# Front_Roof_Enclosure.net
KiCad netlist of a schematic drawn in Altium Designer
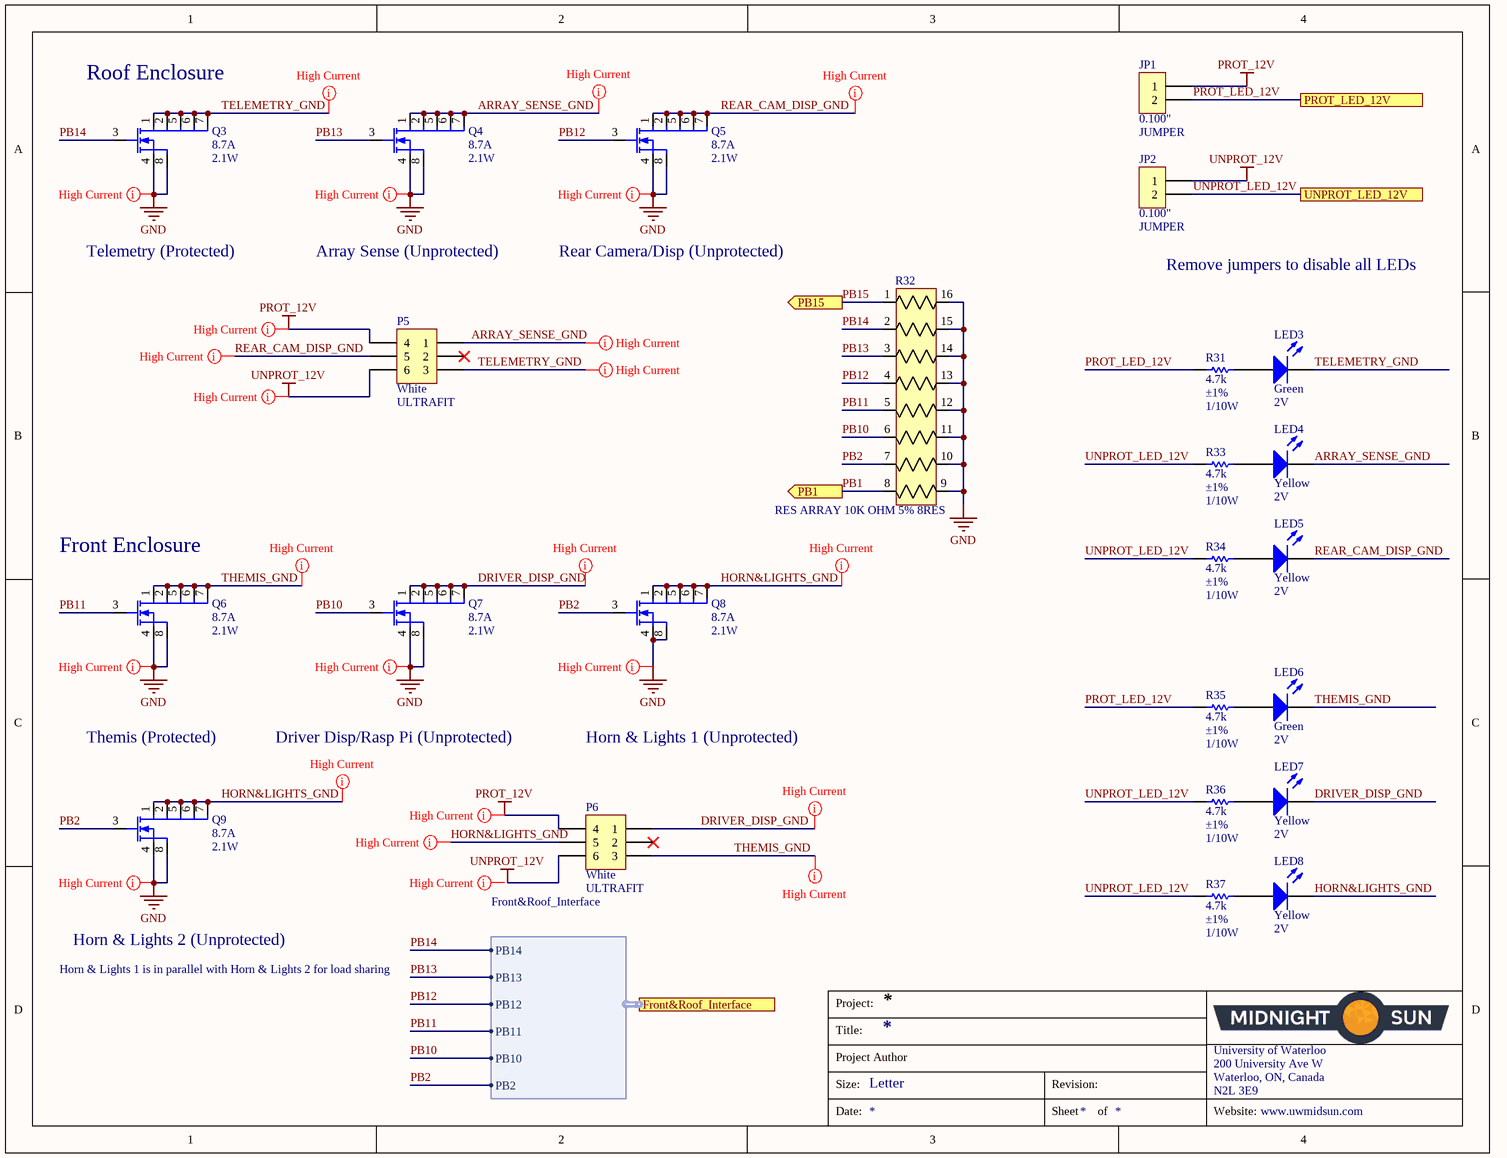
[diagram p0: Front&Roof_Enclosure.SchDoc]

(export (version "E")
  (design (tool "Eeschema 10.0.6"))
  (components
    (comp (ref "JP1")
      (value "JUMPER")
      (footprint "CONN 2POS JUMPER 0.1\"")
      (description "2 Positions Header Connector Through Hole Gold")
      (fields
        (field (name "MANUFACTURER") "Omron Electronics Inc-EMC Div")
        (field (name "MANUFACTURER PART NUMBER") "XG8T-0231")
        (field (name "ROW SPACING - MATING") "0.100\"")
        (field (name "TYPE") "JUMPER")
      )
      (libsource (lib "Schematic Diagrams") (part "CONN 2POS JUMPER 0.1{dblquote}"))
    )
    (comp (ref "JP2")
      (value "JUMPER")
      (footprint "CONN 2POS JUMPER 0.1\"")
      (description "2 Positions Header Connector Through Hole Gold")
      (fields
        (field (name "MANUFACTURER") "Omron Electronics Inc-EMC Div")
        (field (name "MANUFACTURER PART NUMBER") "XG8T-0231")
        (field (name "ROW SPACING - MATING") "0.100\"")
        (field (name "TYPE") "JUMPER")
      )
      (libsource (lib "Schematic Diagrams") (part "CONN 2POS JUMPER 0.1{dblquote}"))
    )
    (comp (ref "LED3")
      (value "LED GREEN CLEAR 2V 0603")
      (footprint "LED_0603")
      (description "Green 572nm LED Indication - Discrete 2V 0603 (1608 Metric)")
      (fields
        (field (name "COLOR") "Green")
        (field (name "VOLTAGE - FORWARD (VF) (TYP)") "2V")
        (field (name "MANUFACTURER") "Wurth Electronics Inc.")
        (field (name "MANUFACTURER PART NUMBER") "150060VS75000")
      )
      (libsource (lib "Schematic Diagrams") (part "LED GREEN CLEAR 2V 0603"))
    )
    (comp (ref "LED4")
      (value "LED YELLOW CLEAR 2.1V 0603")
      (footprint "LED_0603")
      (description "Yellow 590nm LED Indication - Discrete 2V 0603 (1608 Metric)")
      (fields
        (field (name "VOLTAGE - FORWARD (VF) (TYP)") "2V")
        (field (name "MANUFACTURER") "Wurth Electronics Inc.")
        (field (name "MANUFACTURER PART NUMBER") "150060YS75000")
      )
      (libsource (lib "Schematic Diagrams") (part "LED YELLOW CLEAR 2.1V 0603"))
    )
    (comp (ref "LED5")
      (value "LED YELLOW CLEAR 2.1V 0603")
      (footprint "LED_0603")
      (description "Yellow 590nm LED Indication - Discrete 2V 0603 (1608 Metric)")
      (fields
        (field (name "VOLTAGE - FORWARD (VF) (TYP)") "2V")
        (field (name "MANUFACTURER") "Wurth Electronics Inc.")
        (field (name "MANUFACTURER PART NUMBER") "150060YS75000")
      )
      (libsource (lib "Schematic Diagrams") (part "LED YELLOW CLEAR 2.1V 0603"))
    )
    (comp (ref "LED6")
      (value "LED GREEN CLEAR 2V 0603")
      (footprint "LED_0603")
      (description "Green 572nm LED Indication - Discrete 2V 0603 (1608 Metric)")
      (fields
        (field (name "COLOR") "Green")
        (field (name "VOLTAGE - FORWARD (VF) (TYP)") "2V")
        (field (name "MANUFACTURER") "Wurth Electronics Inc.")
        (field (name "MANUFACTURER PART NUMBER") "150060VS75000")
      )
      (libsource (lib "Schematic Diagrams") (part "LED GREEN CLEAR 2V 0603"))
    )
    (comp (ref "LED7")
      (value "LED YELLOW CLEAR 2.1V 0603")
      (footprint "LED_0603")
      (description "Yellow 590nm LED Indication - Discrete 2V 0603 (1608 Metric)")
      (fields
        (field (name "VOLTAGE - FORWARD (VF) (TYP)") "2V")
        (field (name "MANUFACTURER") "Wurth Electronics Inc.")
        (field (name "MANUFACTURER PART NUMBER") "150060YS75000")
      )
      (libsource (lib "Schematic Diagrams") (part "LED YELLOW CLEAR 2.1V 0603"))
    )
    (comp (ref "LED8")
      (value "LED YELLOW CLEAR 2.1V 0603")
      (footprint "LED_0603")
      (description "Yellow 590nm LED Indication - Discrete 2V 0603 (1608 Metric)")
      (fields
        (field (name "VOLTAGE - FORWARD (VF) (TYP)") "2V")
        (field (name "MANUFACTURER") "Wurth Electronics Inc.")
        (field (name "MANUFACTURER PART NUMBER") "150060YS75000")
      )
      (libsource (lib "Schematic Diagrams") (part "LED YELLOW CLEAR 2.1V 0603"))
    )
    (comp (ref "P5")
      (value "CONN 6POS ULTRA-FIT NATURAL COLOR 0.138\"")
      (footprint "CONN, 6POS ULTRA-FIT - NATURAL COLOR")
      (description "6 Positions Header Connector 0.138\" (3.50mm) Through Hole Tin")
      (fields (field (name "INSULATION COLOR") "White") (field (name "SERIES") "ULTRAFIT"))
      (libsource (lib "Schematic Diagrams") (part "CONN 6POS ULTRA-FIT NATURAL COLOR 0.138{dblquote}"))
    )
    (comp (ref "P6")
      (value "CONN 6POS ULTRA-FIT NATURAL COLOR 0.138\"")
      (footprint "CONN, 6POS ULTRA-FIT - NATURAL COLOR")
      (description "6 Positions Header Connector 0.138\" (3.50mm) Through Hole Tin")
      (fields (field (name "INSULATION COLOR") "White") (field (name "SERIES") "ULTRAFIT"))
      (libsource (lib "Schematic Diagrams") (part "CONN 6POS ULTRA-FIT NATURAL COLOR 0.138{dblquote}"))
    )
    (comp (ref "Q3")
      (value "MOSFET N-CH 30V 8.7A 2.1W 6-PQFN (2x2)")
      (footprint "MOSFET N-CH 30V 12A 2mmx2mm PQFN")
      (fields
        (field (name "CURRENT - CONTINUOUS DRAIN (ID) @ 25°C") "8.7A")
        (field (name "POWER DISSIPATION (MAX)") "2.1W")
      )
      (libsource (lib "Schematic Diagrams") (part "MOSFET N-CH 30V 8.7A 2.1W 6-PQFN (2x2)"))
    )
    (comp (ref "Q4")
      (value "MOSFET N-CH 30V 8.7A 2.1W 6-PQFN (2x2)")
      (footprint "MOSFET N-CH 30V 12A 2mmx2mm PQFN")
      (fields
        (field (name "CURRENT - CONTINUOUS DRAIN (ID) @ 25°C") "8.7A")
        (field (name "POWER DISSIPATION (MAX)") "2.1W")
      )
      (libsource (lib "Schematic Diagrams") (part "MOSFET N-CH 30V 8.7A 2.1W 6-PQFN (2x2)"))
    )
    (comp (ref "Q5")
      (value "MOSFET N-CH 30V 8.7A 2.1W 6-PQFN (2x2)")
      (footprint "MOSFET N-CH 30V 12A 2mmx2mm PQFN")
      (fields
        (field (name "CURRENT - CONTINUOUS DRAIN (ID) @ 25°C") "8.7A")
        (field (name "POWER DISSIPATION (MAX)") "2.1W")
      )
      (libsource (lib "Schematic Diagrams") (part "MOSFET N-CH 30V 8.7A 2.1W 6-PQFN (2x2)"))
    )
    (comp (ref "Q6")
      (value "MOSFET N-CH 30V 8.7A 2.1W 6-PQFN (2x2)")
      (footprint "MOSFET N-CH 30V 12A 2mmx2mm PQFN")
      (fields
        (field (name "CURRENT - CONTINUOUS DRAIN (ID) @ 25°C") "8.7A")
        (field (name "POWER DISSIPATION (MAX)") "2.1W")
      )
      (libsource (lib "Schematic Diagrams") (part "MOSFET N-CH 30V 8.7A 2.1W 6-PQFN (2x2)"))
    )
    (comp (ref "Q7")
      (value "MOSFET N-CH 30V 8.7A 2.1W 6-PQFN (2x2)")
      (footprint "MOSFET N-CH 30V 12A 2mmx2mm PQFN")
      (fields
        (field (name "CURRENT - CONTINUOUS DRAIN (ID) @ 25°C") "8.7A")
        (field (name "POWER DISSIPATION (MAX)") "2.1W")
      )
      (libsource (lib "Schematic Diagrams") (part "MOSFET N-CH 30V 8.7A 2.1W 6-PQFN (2x2)"))
    )
    (comp (ref "Q8")
      (value "MOSFET N-CH 30V 8.7A 2.1W 6-PQFN (2x2)")
      (footprint "MOSFET N-CH 30V 12A 2mmx2mm PQFN")
      (fields
        (field (name "CURRENT - CONTINUOUS DRAIN (ID) @ 25°C") "8.7A")
        (field (name "POWER DISSIPATION (MAX)") "2.1W")
      )
      (libsource (lib "Schematic Diagrams") (part "MOSFET N-CH 30V 8.7A 2.1W 6-PQFN (2x2)"))
    )
    (comp (ref "Q9")
      (value "MOSFET N-CH 30V 8.7A 2.1W 6-PQFN (2x2)")
      (footprint "MOSFET N-CH 30V 12A 2mmx2mm PQFN")
      (fields
        (field (name "CURRENT - CONTINUOUS DRAIN (ID) @ 25°C") "8.7A")
        (field (name "POWER DISSIPATION (MAX)") "2.1W")
      )
      (libsource (lib "Schematic Diagrams") (part "MOSFET N-CH 30V 8.7A 2.1W 6-PQFN (2x2)"))
    )
    (comp (ref "R31")
      (value "RES 4.7K OHM 1% 1/10W 0603")
      (footprint "RES, 0603")
      (description "4.7k Ohm ±1% 0.1W, 1/10W Chip Resistor 0603 (1608 Metric) Moisture Resistant Thick Film")
      (fields
        (field (name "RESISTANCE (OHMS)") "4.7k")
        (field (name "TOLERANCE") "±1%")
        (field (name "POWER (WATTS)") "1/10W")
      )
      (libsource (lib "Schematic Diagrams") (part "RES 4.7K OHM 1% 1/10W 0603"))
    )
    (comp (ref "R32")
      (value "RES ARRAY 10K OHM 5% 8RES")
      (footprint "RES ARRAY, 8 POS 1506")
      (description "RES ARRAY SMD 10K 5% 62.5mW 1506")
      (fields
        (field (name "MANUFACTURER_PART_NUMBER") "EXB-2HV103JV")
        (field (name "MANUFACTURER") "Panasonic Electronic Components")
        (field (name "COPYRIGHT") "Copyright (C) 2015 Accelerated Designs. All rights reserved")
      )
      (libsource (lib "Schematic Diagrams") (part "RES ARRAY 10K OHM 5% 8RES EXB-2HV103JV"))
    )
    (comp (ref "R33")
      (value "RES 4.7K OHM 1% 1/10W 0603")
      (footprint "RES, 0603")
      (description "4.7k Ohm ±1% 0.1W, 1/10W Chip Resistor 0603 (1608 Metric) Moisture Resistant Thick Film")
      (fields
        (field (name "RESISTANCE (OHMS)") "4.7k")
        (field (name "TOLERANCE") "±1%")
        (field (name "POWER (WATTS)") "1/10W")
      )
      (libsource (lib "Schematic Diagrams") (part "RES 4.7K OHM 1% 1/10W 0603"))
    )
    (comp (ref "R34")
      (value "RES 4.7K OHM 1% 1/10W 0603")
      (footprint "RES, 0603")
      (description "4.7k Ohm ±1% 0.1W, 1/10W Chip Resistor 0603 (1608 Metric) Moisture Resistant Thick Film")
      (fields
        (field (name "RESISTANCE (OHMS)") "4.7k")
        (field (name "TOLERANCE") "±1%")
        (field (name "POWER (WATTS)") "1/10W")
      )
      (libsource (lib "Schematic Diagrams") (part "RES 4.7K OHM 1% 1/10W 0603"))
    )
    (comp (ref "R35")
      (value "RES 4.7K OHM 1% 1/10W 0603")
      (footprint "RES, 0603")
      (description "4.7k Ohm ±1% 0.1W, 1/10W Chip Resistor 0603 (1608 Metric) Moisture Resistant Thick Film")
      (fields
        (field (name "RESISTANCE (OHMS)") "4.7k")
        (field (name "TOLERANCE") "±1%")
        (field (name "POWER (WATTS)") "1/10W")
      )
      (libsource (lib "Schematic Diagrams") (part "RES 4.7K OHM 1% 1/10W 0603"))
    )
    (comp (ref "R36")
      (value "RES 4.7K OHM 1% 1/10W 0603")
      (footprint "RES, 0603")
      (description "4.7k Ohm ±1% 0.1W, 1/10W Chip Resistor 0603 (1608 Metric) Moisture Resistant Thick Film")
      (fields
        (field (name "RESISTANCE (OHMS)") "4.7k")
        (field (name "TOLERANCE") "±1%")
        (field (name "POWER (WATTS)") "1/10W")
      )
      (libsource (lib "Schematic Diagrams") (part "RES 4.7K OHM 1% 1/10W 0603"))
    )
    (comp (ref "R37")
      (value "RES 4.7K OHM 1% 1/10W 0603")
      (footprint "RES, 0603")
      (description "4.7k Ohm ±1% 0.1W, 1/10W Chip Resistor 0603 (1608 Metric) Moisture Resistant Thick Film")
      (fields
        (field (name "RESISTANCE (OHMS)") "4.7k")
        (field (name "TOLERANCE") "±1%")
        (field (name "POWER (WATTS)") "1/10W")
      )
      (libsource (lib "Schematic Diagrams") (part "RES 4.7K OHM 1% 1/10W 0603"))
    )
  )
  (nets
    (net (code "2") (name "/ARRAY_SENSE_GND") (class "Default")
      (node (ref "LED4") (pin "2") (pinfunction "K_2") (pintype "passive"))
      (node (ref "P5") (pin "1") (pinfunction "1_1") (pintype "passive"))
      (node (ref "Q4") (pin "1") (pinfunction "D_1") (pintype "passive"))
      (node (ref "Q4") (pin "2") (pinfunction "D_2") (pintype "passive"))
      (node (ref "Q4") (pin "5") (pinfunction "D_5") (pintype "passive"))
      (node (ref "Q4") (pin "6") (pinfunction "D_6") (pintype "passive"))
      (node (ref "Q4") (pin "7") (pinfunction "D_7") (pintype "passive"))
    )
    (net (code "3") (name "/DRIVER_DISP_GND") (class "Default")
      (node (ref "LED7") (pin "2") (pinfunction "K_2") (pintype "passive"))
      (node (ref "P6") (pin "1") (pinfunction "1_1") (pintype "passive"))
      (node (ref "Q7") (pin "1") (pinfunction "D_1") (pintype "passive"))
      (node (ref "Q7") (pin "2") (pinfunction "D_2") (pintype "passive"))
      (node (ref "Q7") (pin "5") (pinfunction "D_5") (pintype "passive"))
      (node (ref "Q7") (pin "6") (pinfunction "D_6") (pintype "passive"))
      (node (ref "Q7") (pin "7") (pinfunction "D_7") (pintype "passive"))
    )
    (net (code "4") (name "/HORN&LIGHTS_GND") (class "Default")
      (node (ref "LED8") (pin "2") (pinfunction "K_2") (pintype "passive"))
      (node (ref "P6") (pin "5") (pinfunction "5_5") (pintype "passive"))
      (node (ref "Q8") (pin "1") (pinfunction "D_1") (pintype "passive"))
      (node (ref "Q8") (pin "2") (pinfunction "D_2") (pintype "passive"))
      (node (ref "Q8") (pin "5") (pinfunction "D_5") (pintype "passive"))
      (node (ref "Q8") (pin "6") (pinfunction "D_6") (pintype "passive"))
      (node (ref "Q8") (pin "7") (pinfunction "D_7") (pintype "passive"))
      (node (ref "Q9") (pin "1") (pinfunction "D_1") (pintype "passive"))
      (node (ref "Q9") (pin "2") (pinfunction "D_2") (pintype "passive"))
      (node (ref "Q9") (pin "5") (pinfunction "D_5") (pintype "passive"))
      (node (ref "Q9") (pin "6") (pinfunction "D_6") (pintype "passive"))
      (node (ref "Q9") (pin "7") (pinfunction "D_7") (pintype "passive"))
    )
    (net (code "5") (name "/PB1") (class "Default")
      (node (ref "R32") (pin "8") (pinfunction "8_8") (pintype "passive"))
    )
    (net (code "6") (name "/PB2") (class "Default")
      (node (ref "Q8") (pin "3") (pinfunction "G_3") (pintype "passive"))
      (node (ref "Q9") (pin "3") (pinfunction "G_3") (pintype "passive"))
      (node (ref "R32") (pin "7") (pinfunction "7_7") (pintype "passive"))
    )
    (net (code "7") (name "/PB10") (class "Default")
      (node (ref "Q7") (pin "3") (pinfunction "G_3") (pintype "passive"))
      (node (ref "R32") (pin "6") (pinfunction "6_6") (pintype "passive"))
    )
    (net (code "8") (name "/PB11") (class "Default")
      (node (ref "Q6") (pin "3") (pinfunction "G_3") (pintype "passive"))
      (node (ref "R32") (pin "5") (pinfunction "5_5") (pintype "passive"))
    )
    (net (code "9") (name "/PB12") (class "Default")
      (node (ref "Q5") (pin "3") (pinfunction "G_3") (pintype "passive"))
      (node (ref "R32") (pin "4") (pinfunction "4_4") (pintype "passive"))
    )
    (net (code "10") (name "/PB13") (class "Default")
      (node (ref "Q4") (pin "3") (pinfunction "G_3") (pintype "passive"))
      (node (ref "R32") (pin "3") (pinfunction "3_3") (pintype "passive"))
    )
    (net (code "11") (name "/PB14") (class "Default")
      (node (ref "Q3") (pin "3") (pinfunction "G_3") (pintype "passive"))
      (node (ref "R32") (pin "2") (pinfunction "2_2") (pintype "passive"))
    )
    (net (code "12") (name "/PB15") (class "Default")
      (node (ref "R32") (pin "1") (pinfunction "1_1") (pintype "passive"))
    )
    (net (code "13") (name "/PROT_LED_12V") (class "Default")
      (node (ref "JP1") (pin "2") (pinfunction "2_2") (pintype "passive"))
      (node (ref "R31") (pin "1") (pinfunction "1_1") (pintype "passive"))
      (node (ref "R35") (pin "1") (pinfunction "1_1") (pintype "passive"))
    )
    (net (code "14") (name "/REAR_CAM_DISP_GND") (class "Default")
      (node (ref "LED5") (pin "2") (pinfunction "K_2") (pintype "passive"))
      (node (ref "P5") (pin "5") (pinfunction "5_5") (pintype "passive"))
      (node (ref "Q5") (pin "1") (pinfunction "D_1") (pintype "passive"))
      (node (ref "Q5") (pin "2") (pinfunction "D_2") (pintype "passive"))
      (node (ref "Q5") (pin "5") (pinfunction "D_5") (pintype "passive"))
      (node (ref "Q5") (pin "6") (pinfunction "D_6") (pintype "passive"))
      (node (ref "Q5") (pin "7") (pinfunction "D_7") (pintype "passive"))
    )
    (net (code "15") (name "/TELEMETRY_GND") (class "Default")
      (node (ref "LED3") (pin "2") (pinfunction "K_2") (pintype "passive"))
      (node (ref "P5") (pin "3") (pinfunction "3_3") (pintype "passive"))
      (node (ref "Q3") (pin "1") (pinfunction "D_1") (pintype "passive"))
      (node (ref "Q3") (pin "2") (pinfunction "D_2") (pintype "passive"))
      (node (ref "Q3") (pin "5") (pinfunction "D_5") (pintype "passive"))
      (node (ref "Q3") (pin "6") (pinfunction "D_6") (pintype "passive"))
      (node (ref "Q3") (pin "7") (pinfunction "D_7") (pintype "passive"))
    )
    (net (code "16") (name "/THEMIS_GND") (class "Default")
      (node (ref "LED6") (pin "2") (pinfunction "K_2") (pintype "passive"))
      (node (ref "P6") (pin "3") (pinfunction "3_3") (pintype "passive"))
      (node (ref "Q6") (pin "1") (pinfunction "D_1") (pintype "passive"))
      (node (ref "Q6") (pin "2") (pinfunction "D_2") (pintype "passive"))
      (node (ref "Q6") (pin "5") (pinfunction "D_5") (pintype "passive"))
      (node (ref "Q6") (pin "6") (pinfunction "D_6") (pintype "passive"))
      (node (ref "Q6") (pin "7") (pinfunction "D_7") (pintype "passive"))
    )
    (net (code "17") (name "/UNPROT_LED_12V") (class "Default")
      (node (ref "JP2") (pin "2") (pinfunction "2_2") (pintype "passive"))
      (node (ref "R33") (pin "1") (pinfunction "1_1") (pintype "passive"))
      (node (ref "R34") (pin "1") (pinfunction "1_1") (pintype "passive"))
      (node (ref "R36") (pin "1") (pinfunction "1_1") (pintype "passive"))
      (node (ref "R37") (pin "1") (pinfunction "1_1") (pintype "passive"))
    )
    (net (code "19") (name "GND") (class "Default")
      (node (ref "Q3") (pin "4") (pinfunction "S_4") (pintype "passive"))
      (node (ref "Q3") (pin "8") (pinfunction "S_8") (pintype "passive"))
      (node (ref "Q4") (pin "4") (pinfunction "S_4") (pintype "passive"))
      (node (ref "Q4") (pin "8") (pinfunction "S_8") (pintype "passive"))
      (node (ref "Q5") (pin "4") (pinfunction "S_4") (pintype "passive"))
      (node (ref "Q5") (pin "8") (pinfunction "S_8") (pintype "passive"))
      (node (ref "Q6") (pin "4") (pinfunction "S_4") (pintype "passive"))
      (node (ref "Q6") (pin "8") (pinfunction "S_8") (pintype "passive"))
      (node (ref "Q7") (pin "4") (pinfunction "S_4") (pintype "passive"))
      (node (ref "Q7") (pin "8") (pinfunction "S_8") (pintype "passive"))
      (node (ref "Q8") (pin "4") (pinfunction "S_4") (pintype "passive"))
      (node (ref "Q8") (pin "8") (pinfunction "S_8") (pintype "passive"))
      (node (ref "Q9") (pin "4") (pinfunction "S_4") (pintype "passive"))
      (node (ref "Q9") (pin "8") (pinfunction "S_8") (pintype "passive"))
      (node (ref "R32") (pin "10") (pinfunction "10_10") (pintype "passive"))
      (node (ref "R32") (pin "11") (pinfunction "11_11") (pintype "passive"))
      (node (ref "R32") (pin "12") (pinfunction "12_12") (pintype "passive"))
      (node (ref "R32") (pin "13") (pinfunction "13_13") (pintype "passive"))
      (node (ref "R32") (pin "14") (pinfunction "14_14") (pintype "passive"))
      (node (ref "R32") (pin "15") (pinfunction "15_15") (pintype "passive"))
      (node (ref "R32") (pin "16") (pinfunction "16_16") (pintype "passive"))
      (node (ref "R32") (pin "9") (pinfunction "9_9") (pintype "passive"))
    )
    (net (code "20") (name "Net-(LED3-A)") (class "Default")
      (node (ref "LED3") (pin "1") (pinfunction "A_1") (pintype "passive"))
      (node (ref "R31") (pin "2") (pinfunction "2_2") (pintype "passive"))
    )
    (net (code "21") (name "Net-(LED4-A)") (class "Default")
      (node (ref "LED4") (pin "1") (pinfunction "A_1") (pintype "passive"))
      (node (ref "R33") (pin "2") (pinfunction "2_2") (pintype "passive"))
    )
    (net (code "22") (name "Net-(LED5-A)") (class "Default")
      (node (ref "LED5") (pin "1") (pinfunction "A_1") (pintype "passive"))
      (node (ref "R34") (pin "2") (pinfunction "2_2") (pintype "passive"))
    )
    (net (code "23") (name "Net-(LED6-A)") (class "Default")
      (node (ref "LED6") (pin "1") (pinfunction "A_1") (pintype "passive"))
      (node (ref "R35") (pin "2") (pinfunction "2_2") (pintype "passive"))
    )
    (net (code "24") (name "Net-(LED7-A)") (class "Default")
      (node (ref "LED7") (pin "1") (pinfunction "A_1") (pintype "passive"))
      (node (ref "R36") (pin "2") (pinfunction "2_2") (pintype "passive"))
    )
    (net (code "25") (name "Net-(LED8-A)") (class "Default")
      (node (ref "LED8") (pin "1") (pinfunction "A_1") (pintype "passive"))
      (node (ref "R37") (pin "2") (pinfunction "2_2") (pintype "passive"))
    )
    (net (code "26") (name "PROT_12V") (class "Default")
      (node (ref "JP1") (pin "1") (pinfunction "1_1") (pintype "passive"))
      (node (ref "P5") (pin "4") (pinfunction "4_4") (pintype "passive"))
      (node (ref "P6") (pin "4") (pinfunction "4_4") (pintype "passive"))
    )
    (net (code "27") (name "UNPROT_12V") (class "Default")
      (node (ref "JP2") (pin "1") (pinfunction "1_1") (pintype "passive"))
      (node (ref "P5") (pin "6") (pinfunction "6_6") (pintype "passive"))
      (node (ref "P6") (pin "6") (pinfunction "6_6") (pintype "passive"))
    )
    (net (code "28") (name "unconnected-(P5-Pad2)") (class "Default")
      (node (ref "P5") (pin "2") (pinfunction "2_2") (pintype "passive+no_connect"))
    )
    (net (code "29") (name "unconnected-(P6-Pad2)") (class "Default")
      (node (ref "P6") (pin "2") (pinfunction "2_2") (pintype "passive+no_connect"))
    )
  )
)
